# tm5_redraw.net
KiCad netlist of a schematic drawn in EAGLE
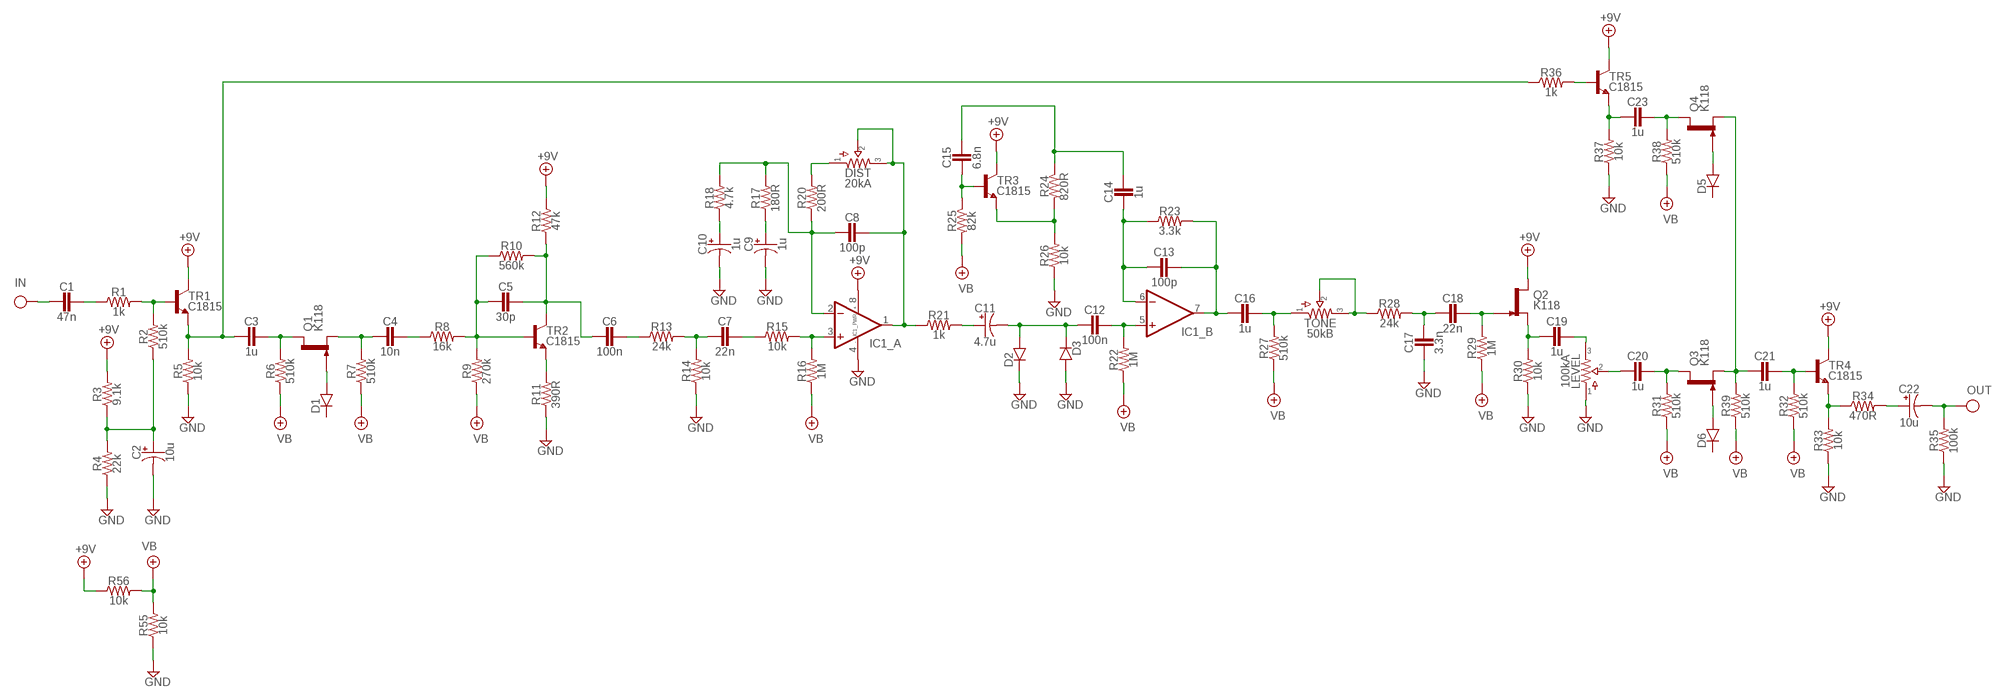
[diagram p0: schematic, sheet 1]

(export (version "E")
  (design (tool "Eeschema 10.0.6"))
  (components
    (comp (ref "C1")
      (value "47n")
      (footprint "eagle-import:BOX_SMALL")
      (libsource (lib "eagle-import") (part "CER/FILMBOX.1"))
    )
    (comp (ref "C2")
      (value "10u")
      (footprint "eagle-import:050_020")
      (libsource (lib "eagle-import") (part "0500"))
    )
    (comp (ref "C3")
      (value "1u")
      (footprint "eagle-import:BOX_SMALL")
      (libsource (lib "eagle-import") (part "CER/FILMBOX.1"))
    )
    (comp (ref "C4")
      (value "10n")
      (footprint "eagle-import:BOX_SMALL")
      (libsource (lib "eagle-import") (part "CER/FILMBOX.1"))
    )
    (comp (ref "C5")
      (value "30p")
      (footprint "eagle-import:BOX_SMALL")
      (libsource (lib "eagle-import") (part "CER/FILMBOX.1"))
    )
    (comp (ref "C6")
      (value "100n")
      (footprint "eagle-import:BOX_SMALL")
      (libsource (lib "eagle-import") (part "CER/FILMBOX.1"))
    )
    (comp (ref "C7")
      (value "22n")
      (footprint "eagle-import:BOX_SMALL")
      (libsource (lib "eagle-import") (part "CER/FILMBOX.1"))
    )
    (comp (ref "C8")
      (value "100p")
      (footprint "eagle-import:BOX_SMALL")
      (libsource (lib "eagle-import") (part "CER/FILMBOX.1"))
    )
    (comp (ref "C9")
      (value "1u")
      (footprint "eagle-import:050_020")
      (libsource (lib "eagle-import") (part "0500"))
    )
    (comp (ref "C10")
      (value "1u")
      (footprint "eagle-import:050_020")
      (libsource (lib "eagle-import") (part "0500"))
    )
    (comp (ref "C11")
      (value "4.7u")
      (footprint "eagle-import:050_020")
      (libsource (lib "eagle-import") (part "0500"))
    )
    (comp (ref "C12")
      (value "100n")
      (footprint "eagle-import:BOX_SMALL")
      (libsource (lib "eagle-import") (part "CER/FILMBOX.1"))
    )
    (comp (ref "C13")
      (value "100p")
      (footprint "eagle-import:BOX_SMALL")
      (libsource (lib "eagle-import") (part "CER/FILMBOX.1"))
    )
    (comp (ref "C14")
      (value "1u")
      (footprint "eagle-import:BOX_SMALL")
      (libsource (lib "eagle-import") (part "CER/FILMBOX.1"))
    )
    (comp (ref "C15")
      (value "6.8n")
      (footprint "eagle-import:BOX_SMALL")
      (libsource (lib "eagle-import") (part "CER/FILMBOX.1"))
    )
    (comp (ref "C16")
      (value "1u")
      (footprint "eagle-import:BOX_SMALL")
      (libsource (lib "eagle-import") (part "CER/FILMBOX.1"))
    )
    (comp (ref "C17")
      (value "3.3n")
      (footprint "eagle-import:BOX_SMALL")
      (libsource (lib "eagle-import") (part "CER/FILMBOX.1"))
    )
    (comp (ref "C18")
      (value "22n")
      (footprint "eagle-import:BOX_SMALL")
      (libsource (lib "eagle-import") (part "CER/FILMBOX.1"))
    )
    (comp (ref "C19")
      (value "1u")
      (footprint "eagle-import:BOX_SMALL")
      (libsource (lib "eagle-import") (part "CER/FILMBOX.1"))
    )
    (comp (ref "C20")
      (value "1u")
      (footprint "eagle-import:BOX_SMALL")
      (libsource (lib "eagle-import") (part "CER/FILMBOX.1"))
    )
    (comp (ref "C21")
      (value "1u")
      (footprint "eagle-import:BOX_SMALL")
      (libsource (lib "eagle-import") (part "CER/FILMBOX.1"))
    )
    (comp (ref "C22")
      (value "10u")
      (footprint "eagle-import:050_020")
      (libsource (lib "eagle-import") (part "0500"))
    )
    (comp (ref "C23")
      (value "1u")
      (footprint "eagle-import:BOX_SMALL")
      (libsource (lib "eagle-import") (part "CER/FILMBOX.1"))
    )
    (comp (ref "D1")
      (value "DO35.2")
      (footprint "eagle-import:DO35-2")
      (libsource (lib "eagle-import") (part "DO35.2"))
    )
    (comp (ref "D2")
      (value "DO35.2")
      (footprint "eagle-import:DO35-2")
      (libsource (lib "eagle-import") (part "DO35.2"))
    )
    (comp (ref "D3")
      (value "DO35.2")
      (footprint "eagle-import:DO35-2")
      (libsource (lib "eagle-import") (part "DO35.2"))
    )
    (comp (ref "D5")
      (value "DO35.2")
      (footprint "eagle-import:DO35-2")
      (libsource (lib "eagle-import") (part "DO35.2"))
    )
    (comp (ref "D6")
      (value "DO35.2")
      (footprint "eagle-import:DO35-2")
      (libsource (lib "eagle-import") (part "DO35.2"))
    )
    (comp (ref "DIST")
      (value "20kA")
      (footprint "eagle-import:16MM")
      (libsource (lib "eagle-import") (part "POTS16MM"))
    )
    (comp (ref "IC1")
      (value "DUALTH")
      (footprint "eagle-import:DIL0")
      (libsource (lib "eagle-import") (part "DUALTH"))
    )
    (comp (ref "LEVEL")
      (value "100kA")
      (footprint "eagle-import:16MM")
      (libsource (lib "eagle-import") (part "POTS16MM"))
    )
    (comp (ref "Q1")
      (value "K118")
      (footprint "eagle-import:TO92-")
      (libsource (lib "eagle-import") (part "2N3819TO-92S"))
    )
    (comp (ref "Q2")
      (value "K118")
      (footprint "eagle-import:TO92-")
      (libsource (lib "eagle-import") (part "2N3819TO-92S"))
    )
    (comp (ref "Q3")
      (value "K118")
      (footprint "eagle-import:TO92-")
      (libsource (lib "eagle-import") (part "2N3819TO-92S"))
    )
    (comp (ref "Q4")
      (value "K118")
      (footprint "eagle-import:TO92-")
      (libsource (lib "eagle-import") (part "2N3819TO-92S"))
    )
    (comp (ref "R1")
      (value "1k")
      (footprint "eagle-import:R0207_3")
      (libsource (lib "eagle-import") (part "R_.3B"))
    )
    (comp (ref "R2")
      (value "510k")
      (footprint "eagle-import:R0207_3")
      (libsource (lib "eagle-import") (part "R_.3B"))
    )
    (comp (ref "R3")
      (value "9.1k")
      (footprint "eagle-import:R0207_3")
      (libsource (lib "eagle-import") (part "R_.3B"))
    )
    (comp (ref "R4")
      (value "22k")
      (footprint "eagle-import:R0207_3")
      (libsource (lib "eagle-import") (part "R_.3B"))
    )
    (comp (ref "R5")
      (value "10k")
      (footprint "eagle-import:R0207_3")
      (libsource (lib "eagle-import") (part "R_.3B"))
    )
    (comp (ref "R6")
      (value "510k")
      (footprint "eagle-import:R0207_3")
      (libsource (lib "eagle-import") (part "R_.3B"))
    )
    (comp (ref "R7")
      (value "510k")
      (footprint "eagle-import:R0207_3")
      (libsource (lib "eagle-import") (part "R_.3B"))
    )
    (comp (ref "R8")
      (value "16k")
      (footprint "eagle-import:R0207_3")
      (libsource (lib "eagle-import") (part "R_.3B"))
    )
    (comp (ref "R9")
      (value "270k")
      (footprint "eagle-import:R0207_3")
      (libsource (lib "eagle-import") (part "R_.3B"))
    )
    (comp (ref "R10")
      (value "560k")
      (footprint "eagle-import:R0207_3")
      (libsource (lib "eagle-import") (part "R_.3B"))
    )
    (comp (ref "R11")
      (value "390R")
      (footprint "eagle-import:R0207_3")
      (libsource (lib "eagle-import") (part "R_.3B"))
    )
    (comp (ref "R12")
      (value "47k")
      (footprint "eagle-import:R0207_3")
      (libsource (lib "eagle-import") (part "R_.3B"))
    )
    (comp (ref "R13")
      (value "24k")
      (footprint "eagle-import:R0207_3")
      (libsource (lib "eagle-import") (part "R_.3B"))
    )
    (comp (ref "R14")
      (value "10k")
      (footprint "eagle-import:R0207_3")
      (libsource (lib "eagle-import") (part "R_.3B"))
    )
    (comp (ref "R15")
      (value "10k")
      (footprint "eagle-import:R0207_3")
      (libsource (lib "eagle-import") (part "R_.3B"))
    )
    (comp (ref "R16")
      (value "1M")
      (footprint "eagle-import:R0207_3")
      (libsource (lib "eagle-import") (part "R_.3B"))
    )
    (comp (ref "R17")
      (value "180R")
      (footprint "eagle-import:R0207_3")
      (libsource (lib "eagle-import") (part "R_.3B"))
    )
    (comp (ref "R18")
      (value "4.7k")
      (footprint "eagle-import:R0207_3")
      (libsource (lib "eagle-import") (part "R_.3B"))
    )
    (comp (ref "R20")
      (value "200R")
      (footprint "eagle-import:R0207_3")
      (libsource (lib "eagle-import") (part "R_.3B"))
    )
    (comp (ref "R21")
      (value "1k")
      (footprint "eagle-import:R0207_3")
      (libsource (lib "eagle-import") (part "R_.3B"))
    )
    (comp (ref "R22")
      (value "1M")
      (footprint "eagle-import:R0207_3")
      (libsource (lib "eagle-import") (part "R_.3B"))
    )
    (comp (ref "R23")
      (value "3.3k")
      (footprint "eagle-import:R0207_3")
      (libsource (lib "eagle-import") (part "R_.3B"))
    )
    (comp (ref "R24")
      (value "820R")
      (footprint "eagle-import:R0207_3")
      (libsource (lib "eagle-import") (part "R_.3B"))
    )
    (comp (ref "R25")
      (value "82k")
      (footprint "eagle-import:R0207_3")
      (libsource (lib "eagle-import") (part "R_.3B"))
    )
    (comp (ref "R26")
      (value "10k")
      (footprint "eagle-import:R0207_3")
      (libsource (lib "eagle-import") (part "R_.3B"))
    )
    (comp (ref "R27")
      (value "510k")
      (footprint "eagle-import:R0207_3")
      (libsource (lib "eagle-import") (part "R_.3B"))
    )
    (comp (ref "R28")
      (value "24k")
      (footprint "eagle-import:R0207_3")
      (libsource (lib "eagle-import") (part "R_.3B"))
    )
    (comp (ref "R29")
      (value "1M")
      (footprint "eagle-import:R0207_3")
      (libsource (lib "eagle-import") (part "R_.3B"))
    )
    (comp (ref "R30")
      (value "10k")
      (footprint "eagle-import:R0207_3")
      (libsource (lib "eagle-import") (part "R_.3B"))
    )
    (comp (ref "R31")
      (value "510k")
      (footprint "eagle-import:R0207_3")
      (libsource (lib "eagle-import") (part "R_.3B"))
    )
    (comp (ref "R32")
      (value "510k")
      (footprint "eagle-import:R0207_3")
      (libsource (lib "eagle-import") (part "R_.3B"))
    )
    (comp (ref "R33")
      (value "10k")
      (footprint "eagle-import:R0207_3")
      (libsource (lib "eagle-import") (part "R_.3B"))
    )
    (comp (ref "R34")
      (value "470R")
      (footprint "eagle-import:R0207_3")
      (libsource (lib "eagle-import") (part "R_.3B"))
    )
    (comp (ref "R35")
      (value "100k")
      (footprint "eagle-import:R0207_3")
      (libsource (lib "eagle-import") (part "R_.3B"))
    )
    (comp (ref "R36")
      (value "1k")
      (footprint "eagle-import:R0207_3")
      (libsource (lib "eagle-import") (part "R_.3B"))
    )
    (comp (ref "R37")
      (value "10k")
      (footprint "eagle-import:R0207_3")
      (libsource (lib "eagle-import") (part "R_.3B"))
    )
    (comp (ref "R38")
      (value "510k")
      (footprint "eagle-import:R0207_3")
      (libsource (lib "eagle-import") (part "R_.3B"))
    )
    (comp (ref "R39")
      (value "510k")
      (footprint "eagle-import:R0207_3")
      (libsource (lib "eagle-import") (part "R_.3B"))
    )
    (comp (ref "R55")
      (value "10k")
      (footprint "eagle-import:R0207_3")
      (libsource (lib "eagle-import") (part "R_.3B"))
    )
    (comp (ref "R56")
      (value "10k")
      (footprint "eagle-import:R0207_3")
      (libsource (lib "eagle-import") (part "R_.3B"))
    )
    (comp (ref "TONE")
      (value "50kB")
      (footprint "eagle-import:16MM")
      (libsource (lib "eagle-import") (part "POTS16MM"))
    )
    (comp (ref "TR1")
      (value "C1815")
      (footprint "eagle-import:TO92-")
      (libsource (lib "eagle-import") (part "2SC828A"))
    )
    (comp (ref "TR2")
      (value "C1815")
      (footprint "eagle-import:TO92-")
      (libsource (lib "eagle-import") (part "2SC828A"))
    )
    (comp (ref "TR3")
      (value "C1815")
      (footprint "eagle-import:TO92-")
      (libsource (lib "eagle-import") (part "2SC828A"))
    )
    (comp (ref "TR4")
      (value "C1815")
      (footprint "eagle-import:TO92-")
      (libsource (lib "eagle-import") (part "2SC828A"))
    )
    (comp (ref "TR5")
      (value "C1815")
      (footprint "eagle-import:TO92-")
      (libsource (lib "eagle-import") (part "2SC828A"))
    )
  )
  (nets
    (net (code "1") (name "+9V") (class "Default")
      (node (ref "IC1") (pin "8") (pinfunction "V+_8") (pintype "power_in"))
      (node (ref "Q2") (pin "3") (pinfunction "D_3") (pintype "passive"))
      (node (ref "R12") (pin "2") (pinfunction "2_2") (pintype "passive"))
      (node (ref "R3") (pin "2") (pinfunction "2_2") (pintype "passive"))
      (node (ref "R56") (pin "1") (pinfunction "1_1") (pintype "passive"))
      (node (ref "TR1") (pin "2") (pinfunction "C_2") (pintype "passive"))
      (node (ref "TR3") (pin "2") (pinfunction "C_2") (pintype "passive"))
      (node (ref "TR4") (pin "2") (pinfunction "C_2") (pintype "passive"))
      (node (ref "TR5") (pin "2") (pinfunction "C_2") (pintype "passive"))
    )
    (net (code "2") (name "GND") (class "Default")
      (node (ref "C10") (pin "-") (pinfunction "-_-") (pintype "passive"))
      (node (ref "C17") (pin "2") (pinfunction "2_2") (pintype "passive"))
      (node (ref "C2") (pin "-") (pinfunction "-_-") (pintype "passive"))
      (node (ref "C9") (pin "-") (pinfunction "-_-") (pintype "passive"))
      (node (ref "D2") (pin "C") (pinfunction "C_C") (pintype "passive"))
      (node (ref "D3") (pin "A") (pinfunction "A_A") (pintype "passive"))
      (node (ref "IC1") (pin "4") (pinfunction "V-_4") (pintype "power_in"))
      (node (ref "LEVEL") (pin "1") (pinfunction "1_1") (pintype "passive"))
      (node (ref "R11") (pin "1") (pinfunction "1_1") (pintype "passive"))
      (node (ref "R14") (pin "1") (pinfunction "1_1") (pintype "passive"))
      (node (ref "R26") (pin "1") (pinfunction "1_1") (pintype "passive"))
      (node (ref "R30") (pin "1") (pinfunction "1_1") (pintype "passive"))
      (node (ref "R33") (pin "1") (pinfunction "1_1") (pintype "passive"))
      (node (ref "R35") (pin "1") (pinfunction "1_1") (pintype "passive"))
      (node (ref "R37") (pin "1") (pinfunction "1_1") (pintype "passive"))
      (node (ref "R4") (pin "1") (pinfunction "1_1") (pintype "passive"))
      (node (ref "R5") (pin "1") (pinfunction "1_1") (pintype "passive"))
      (node (ref "R55") (pin "1") (pinfunction "1_1") (pintype "passive"))
    )
    (net (code "3") (name "IN") (class "Default")
      (node (ref "C1") (pin "2") (pinfunction "2_2") (pintype "passive"))
    )
    (net (code "4") (name "Net-(C1-Pad1)") (class "Default")
      (node (ref "C1") (pin "1") (pinfunction "1_1") (pintype "passive"))
      (node (ref "R1") (pin "1") (pinfunction "1_1") (pintype "passive"))
    )
    (net (code "5") (name "Net-(C2-Pad+)") (class "Default")
      (node (ref "C2") (pin "+") (pinfunction "+_+") (pintype "passive"))
      (node (ref "R2") (pin "1") (pinfunction "1_1") (pintype "passive"))
      (node (ref "R3") (pin "1") (pinfunction "1_1") (pintype "passive"))
      (node (ref "R4") (pin "2") (pinfunction "2_2") (pintype "passive"))
    )
    (net (code "6") (name "Net-(C4-Pad1)") (class "Default")
      (node (ref "C4") (pin "1") (pinfunction "1_1") (pintype "passive"))
      (node (ref "R8") (pin "1") (pinfunction "1_1") (pintype "passive"))
    )
    (net (code "7") (name "Net-(C6-Pad1)") (class "Default")
      (node (ref "C6") (pin "1") (pinfunction "1_1") (pintype "passive"))
      (node (ref "R13") (pin "1") (pinfunction "1_1") (pintype "passive"))
    )
    (net (code "8") (name "Net-(C7-Pad1)") (class "Default")
      (node (ref "C7") (pin "1") (pinfunction "1_1") (pintype "passive"))
      (node (ref "R15") (pin "1") (pinfunction "1_1") (pintype "passive"))
    )
    (net (code "9") (name "Net-(C7-Pad2)") (class "Default")
      (node (ref "C7") (pin "2") (pinfunction "2_2") (pintype "passive"))
      (node (ref "R13") (pin "2") (pinfunction "2_2") (pintype "passive"))
      (node (ref "R14") (pin "2") (pinfunction "2_2") (pintype "passive"))
    )
    (net (code "10") (name "Net-(C9-Pad+)") (class "Default")
      (node (ref "C9") (pin "+") (pinfunction "+_+") (pintype "passive"))
      (node (ref "R17") (pin "1") (pinfunction "1_1") (pintype "passive"))
    )
    (net (code "11") (name "Net-(C10-Pad+)") (class "Default")
      (node (ref "C10") (pin "+") (pinfunction "+_+") (pintype "passive"))
      (node (ref "R18") (pin "1") (pinfunction "1_1") (pintype "passive"))
    )
    (net (code "12") (name "Net-(C11-Pad+)") (class "Default")
      (node (ref "C11") (pin "+") (pinfunction "+_+") (pintype "passive"))
      (node (ref "R21") (pin "2") (pinfunction "2_2") (pintype "passive"))
    )
    (net (code "13") (name "Net-(C11-Pad-)") (class "Default")
      (node (ref "C11") (pin "-") (pinfunction "-_-") (pintype "passive"))
      (node (ref "C12") (pin "2") (pinfunction "2_2") (pintype "passive"))
      (node (ref "D2") (pin "A") (pinfunction "A_A") (pintype "passive"))
      (node (ref "D3") (pin "C") (pinfunction "C_C") (pintype "passive"))
    )
    (net (code "14") (name "Net-(C14-Pad1)") (class "Default")
      (node (ref "C14") (pin "1") (pinfunction "1_1") (pintype "passive"))
      (node (ref "C15") (pin "1") (pinfunction "1_1") (pintype "passive"))
      (node (ref "R24") (pin "1") (pinfunction "1_1") (pintype "passive"))
    )
    (net (code "15") (name "Net-(C16-Pad1)") (class "Default")
      (node (ref "C16") (pin "1") (pinfunction "1_1") (pintype "passive"))
      (node (ref "R27") (pin "2") (pinfunction "2_2") (pintype "passive"))
      (node (ref "TONE") (pin "1") (pinfunction "1_1") (pintype "passive"))
    )
    (net (code "16") (name "Net-(C17-Pad1)") (class "Default")
      (node (ref "C17") (pin "1") (pinfunction "1_1") (pintype "passive"))
      (node (ref "C18") (pin "2") (pinfunction "2_2") (pintype "passive"))
      (node (ref "R28") (pin "2") (pinfunction "2_2") (pintype "passive"))
    )
    (net (code "17") (name "Net-(C19-Pad1)") (class "Default")
      (node (ref "C19") (pin "1") (pinfunction "1_1") (pintype "passive"))
      (node (ref "LEVEL") (pin "3") (pinfunction "3_3") (pintype "passive"))
    )
    (net (code "18") (name "Net-(C20-Pad2)") (class "Default")
      (node (ref "C20") (pin "2") (pinfunction "2_2") (pintype "passive"))
      (node (ref "LEVEL") (pin "2") (pinfunction "2_2") (pintype "passive"))
    )
    (net (code "19") (name "Net-(C22-Pad+)") (class "Default")
      (node (ref "C22") (pin "+") (pinfunction "+_+") (pintype "passive"))
      (node (ref "R34") (pin "2") (pinfunction "2_2") (pintype "passive"))
    )
    (net (code "20") (name "Net-(DIST-Pad1)") (class "Default")
      (node (ref "DIST") (pin "1") (pinfunction "1_1") (pintype "passive"))
      (node (ref "R20") (pin "2") (pinfunction "2_2") (pintype "passive"))
    )
    (net (code "21") (name "Net-(IC1A-+IN)") (class "Default")
      (node (ref "IC1") (pin "3") (pinfunction "+IN_3") (pintype "input"))
      (node (ref "R15") (pin "2") (pinfunction "2_2") (pintype "passive"))
      (node (ref "R16") (pin "2") (pinfunction "2_2") (pintype "passive"))
    )
    (net (code "22") (name "Net-(IC1A--IN)") (class "Default")
      (node (ref "C8") (pin "2") (pinfunction "2_2") (pintype "passive"))
      (node (ref "IC1") (pin "2") (pinfunction "-IN_2") (pintype "input"))
      (node (ref "R17") (pin "2") (pinfunction "2_2") (pintype "passive"))
      (node (ref "R18") (pin "2") (pinfunction "2_2") (pintype "passive"))
      (node (ref "R20") (pin "1") (pinfunction "1_1") (pintype "passive"))
    )
    (net (code "23") (name "Net-(IC1A-OUT)") (class "Default")
      (node (ref "C8") (pin "1") (pinfunction "1_1") (pintype "passive"))
      (node (ref "DIST") (pin "2") (pinfunction "2_2") (pintype "passive"))
      (node (ref "DIST") (pin "3") (pinfunction "3_3") (pintype "passive"))
      (node (ref "IC1") (pin "1") (pinfunction "OUT_1") (pintype "output"))
      (node (ref "R21") (pin "1") (pinfunction "1_1") (pintype "passive"))
    )
    (net (code "24") (name "Net-(IC1B-+IN)") (class "Default")
      (node (ref "C12") (pin "1") (pinfunction "1_1") (pintype "passive"))
      (node (ref "IC1") (pin "5") (pinfunction "+IN_5") (pintype "input"))
      (node (ref "R22") (pin "2") (pinfunction "2_2") (pintype "passive"))
    )
    (net (code "25") (name "Net-(IC1B--IN)") (class "Default")
      (node (ref "C13") (pin "2") (pinfunction "2_2") (pintype "passive"))
      (node (ref "C14") (pin "2") (pinfunction "2_2") (pintype "passive"))
      (node (ref "IC1") (pin "6") (pinfunction "-IN_6") (pintype "input"))
      (node (ref "R23") (pin "1") (pinfunction "1_1") (pintype "passive"))
    )
    (net (code "26") (name "Net-(IC1B-OUT)") (class "Default")
      (node (ref "C13") (pin "1") (pinfunction "1_1") (pintype "passive"))
      (node (ref "C16") (pin "2") (pinfunction "2_2") (pintype "passive"))
      (node (ref "IC1") (pin "7") (pinfunction "OUT_7") (pintype "output"))
      (node (ref "R23") (pin "2") (pinfunction "2_2") (pintype "passive"))
    )
    (net (code "27") (name "Net-(Q1-D)") (class "Default")
      (node (ref "C3") (pin "1") (pinfunction "1_1") (pintype "passive"))
      (node (ref "Q1") (pin "3") (pinfunction "D_3") (pintype "passive"))
      (node (ref "R6") (pin "2") (pinfunction "2_2") (pintype "passive"))
    )
    (net (code "28") (name "Net-(Q1-G)") (class "Default")
      (node (ref "D1") (pin "A") (pinfunction "A_A") (pintype "passive"))
      (node (ref "Q1") (pin "2") (pinfunction "G_2") (pintype "passive"))
    )
    (net (code "29") (name "Net-(Q1-S)") (class "Default")
      (node (ref "C4") (pin "2") (pinfunction "2_2") (pintype "passive"))
      (node (ref "Q1") (pin "1") (pinfunction "S_1") (pintype "passive"))
      (node (ref "R7") (pin "2") (pinfunction "2_2") (pintype "passive"))
    )
    (net (code "30") (name "Net-(Q2-G)") (class "Default")
      (node (ref "C18") (pin "1") (pinfunction "1_1") (pintype "passive"))
      (node (ref "Q2") (pin "2") (pinfunction "G_2") (pintype "passive"))
      (node (ref "R29") (pin "2") (pinfunction "2_2") (pintype "passive"))
    )
    (net (code "31") (name "Net-(Q2-S)") (class "Default")
      (node (ref "C19") (pin "2") (pinfunction "2_2") (pintype "passive"))
      (node (ref "Q2") (pin "1") (pinfunction "S_1") (pintype "passive"))
      (node (ref "R30") (pin "2") (pinfunction "2_2") (pintype "passive"))
    )
    (net (code "32") (name "Net-(Q3-D)") (class "Default")
      (node (ref "C20") (pin "1") (pinfunction "1_1") (pintype "passive"))
      (node (ref "Q3") (pin "3") (pinfunction "D_3") (pintype "passive"))
      (node (ref "R31") (pin "2") (pinfunction "2_2") (pintype "passive"))
    )
    (net (code "33") (name "Net-(Q3-G)") (class "Default")
      (node (ref "D6") (pin "A") (pinfunction "A_A") (pintype "passive"))
      (node (ref "Q3") (pin "2") (pinfunction "G_2") (pintype "passive"))
    )
    (net (code "34") (name "Net-(Q3-S)") (class "Default")
      (node (ref "C21") (pin "2") (pinfunction "2_2") (pintype "passive"))
      (node (ref "Q3") (pin "1") (pinfunction "S_1") (pintype "passive"))
      (node (ref "Q4") (pin "1") (pinfunction "S_1") (pintype "passive"))
      (node (ref "R39") (pin "2") (pinfunction "2_2") (pintype "passive"))
    )
    (net (code "35") (name "Net-(Q4-D)") (class "Default")
      (node (ref "C23") (pin "1") (pinfunction "1_1") (pintype "passive"))
      (node (ref "Q4") (pin "3") (pinfunction "D_3") (pintype "passive"))
      (node (ref "R38") (pin "2") (pinfunction "2_2") (pintype "passive"))
    )
    (net (code "36") (name "Net-(Q4-G)") (class "Default")
      (node (ref "D5") (pin "A") (pinfunction "A_A") (pintype "passive"))
      (node (ref "Q4") (pin "2") (pinfunction "G_2") (pintype "passive"))
    )
    (net (code "37") (name "Net-(R28-Pad1)") (class "Default")
      (node (ref "R28") (pin "1") (pinfunction "1_1") (pintype "passive"))
      (node (ref "TONE") (pin "2") (pinfunction "2_2") (pintype "passive"))
      (node (ref "TONE") (pin "3") (pinfunction "3_3") (pintype "passive"))
    )
    (net (code "38") (name "Net-(TR1-B)") (class "Default")
      (node (ref "R1") (pin "2") (pinfunction "2_2") (pintype "passive"))
      (node (ref "R2") (pin "2") (pinfunction "2_2") (pintype "passive"))
      (node (ref "TR1") (pin "1") (pinfunction "B_1") (pintype "passive"))
    )
    (net (code "39") (name "Net-(TR1-E)") (class "Default")
      (node (ref "C3") (pin "2") (pinfunction "2_2") (pintype "passive"))
      (node (ref "R36") (pin "1") (pinfunction "1_1") (pintype "passive"))
      (node (ref "R5") (pin "2") (pinfunction "2_2") (pintype "passive"))
      (node (ref "TR1") (pin "3") (pinfunction "E_3") (pintype "passive"))
    )
    (net (code "40") (name "Net-(TR2-B)") (class "Default")
      (node (ref "C5") (pin "2") (pinfunction "2_2") (pintype "passive"))
      (node (ref "R10") (pin "1") (pinfunction "1_1") (pintype "passive"))
      (node (ref "R8") (pin "2") (pinfunction "2_2") (pintype "passive"))
      (node (ref "R9") (pin "2") (pinfunction "2_2") (pintype "passive"))
      (node (ref "TR2") (pin "1") (pinfunction "B_1") (pintype "passive"))
    )
    (net (code "41") (name "Net-(TR2-C)") (class "Default")
      (node (ref "C5") (pin "1") (pinfunction "1_1") (pintype "passive"))
      (node (ref "C6") (pin "2") (pinfunction "2_2") (pintype "passive"))
      (node (ref "R10") (pin "2") (pinfunction "2_2") (pintype "passive"))
      (node (ref "R12") (pin "1") (pinfunction "1_1") (pintype "passive"))
      (node (ref "TR2") (pin "2") (pinfunction "C_2") (pintype "passive"))
    )
    (net (code "42") (name "Net-(TR2-E)") (class "Default")
      (node (ref "R11") (pin "2") (pinfunction "2_2") (pintype "passive"))
      (node (ref "TR2") (pin "3") (pinfunction "E_3") (pintype "passive"))
    )
    (net (code "43") (name "Net-(TR3-B)") (class "Default")
      (node (ref "C15") (pin "2") (pinfunction "2_2") (pintype "passive"))
      (node (ref "R25") (pin "1") (pinfunction "1_1") (pintype "passive"))
      (node (ref "TR3") (pin "1") (pinfunction "B_1") (pintype "passive"))
    )
    (net (code "44") (name "Net-(TR3-E)") (class "Default")
      (node (ref "R24") (pin "2") (pinfunction "2_2") (pintype "passive"))
      (node (ref "R26") (pin "2") (pinfunction "2_2") (pintype "passive"))
      (node (ref "TR3") (pin "3") (pinfunction "E_3") (pintype "passive"))
    )
    (net (code "45") (name "Net-(TR4-B)") (class "Default")
      (node (ref "C21") (pin "1") (pinfunction "1_1") (pintype "passive"))
      (node (ref "R32") (pin "2") (pinfunction "2_2") (pintype "passive"))
      (node (ref "TR4") (pin "1") (pinfunction "B_1") (pintype "passive"))
    )
    (net (code "46") (name "Net-(TR4-E)") (class "Default")
      (node (ref "R33") (pin "2") (pinfunction "2_2") (pintype "passive"))
      (node (ref "R34") (pin "1") (pinfunction "1_1") (pintype "passive"))
      (node (ref "TR4") (pin "3") (pinfunction "E_3") (pintype "passive"))
    )
    (net (code "47") (name "Net-(TR5-B)") (class "Default")
      (node (ref "R36") (pin "2") (pinfunction "2_2") (pintype "passive"))
      (node (ref "TR5") (pin "1") (pinfunction "B_1") (pintype "passive"))
    )
    (net (code "48") (name "Net-(TR5-E)") (class "Default")
      (node (ref "C23") (pin "2") (pinfunction "2_2") (pintype "passive"))
      (node (ref "R37") (pin "2") (pinfunction "2_2") (pintype "passive"))
      (node (ref "TR5") (pin "3") (pinfunction "E_3") (pintype "passive"))
    )
    (net (code "49") (name "OUT") (class "Default")
      (node (ref "C22") (pin "-") (pinfunction "-_-") (pintype "passive"))
      (node (ref "R35") (pin "2") (pinfunction "2_2") (pintype "passive"))
    )
    (net (code "50") (name "VB") (class "Default")
      (node (ref "R16") (pin "1") (pinfunction "1_1") (pintype "passive"))
      (node (ref "R22") (pin "1") (pinfunction "1_1") (pintype "passive"))
      (node (ref "R25") (pin "2") (pinfunction "2_2") (pintype "passive"))
      (node (ref "R27") (pin "1") (pinfunction "1_1") (pintype "passive"))
      (node (ref "R29") (pin "1") (pinfunction "1_1") (pintype "passive"))
      (node (ref "R31") (pin "1") (pinfunction "1_1") (pintype "passive"))
      (node (ref "R32") (pin "1") (pinfunction "1_1") (pintype "passive"))
      (node (ref "R38") (pin "1") (pinfunction "1_1") (pintype "passive"))
      (node (ref "R39") (pin "1") (pinfunction "1_1") (pintype "passive"))
      (node (ref "R55") (pin "2") (pinfunction "2_2") (pintype "passive"))
      (node (ref "R56") (pin "2") (pinfunction "2_2") (pintype "passive"))
      (node (ref "R6") (pin "1") (pinfunction "1_1") (pintype "passive"))
      (node (ref "R7") (pin "1") (pinfunction "1_1") (pintype "passive"))
      (node (ref "R9") (pin "1") (pinfunction "1_1") (pintype "passive"))
    )
    (net (code "51") (name "unconnected-(D1-PadC)") (class "Default")
      (node (ref "D1") (pin "C") (pinfunction "C_C") (pintype "passive"))
    )
    (net (code "52") (name "unconnected-(D5-PadC)") (class "Default")
      (node (ref "D5") (pin "C") (pinfunction "C_C") (pintype "passive"))
    )
    (net (code "53") (name "unconnected-(D6-PadC)") (class "Default")
      (node (ref "D6") (pin "C") (pinfunction "C_C") (pintype "passive"))
    )
  )
)
